# hub.net
KiCad netlist of a schematic drawn in Altium Designer
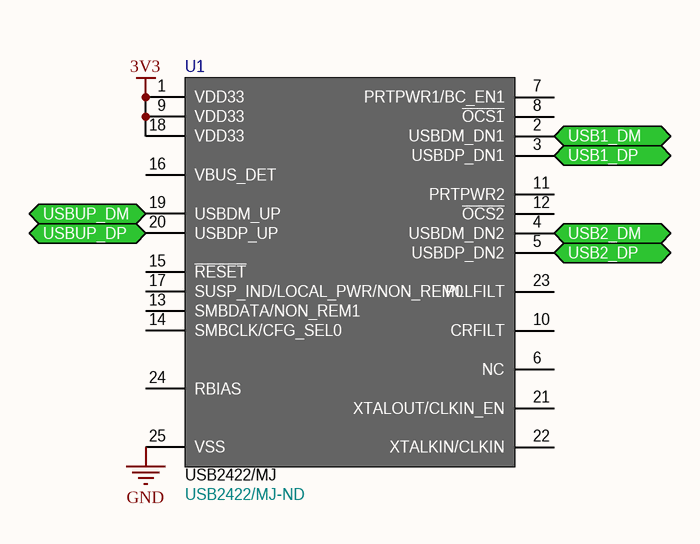
[diagram p0: hub.SchDoc]

(export (version "E")
  (design (tool "Eeschema 10.0.6"))
  (components
    (comp (ref "U1")
      (value "USB2422/MJ")
      (footprint "QFN50P400X400-24V2N")
      (description "IC HUB CTLR USB 2.0 24QFN")
      (fields
        (field (name "MANUFACTURER") "Microchip Technology")
        (field (name "BASE PART NUMBER") "USB2422")
        (field (name "SUPPLIER PART NUMBER 1") "USB2422/MJ-ND")
      )
      (libsource (lib "Microchip Interface") (part "USB2422/MJ"))
    )
  )
  (nets
    (net (code "1") (name "/USB1_DM") (class "Default")
      (node (ref "U1") (pin "2") (pinfunction "USBDM_DN1_2") (pintype "passive"))
    )
    (net (code "2") (name "/USB1_DP") (class "Default")
      (node (ref "U1") (pin "3") (pinfunction "USBDP_DN1_3") (pintype "passive"))
    )
    (net (code "3") (name "/USB2_DM") (class "Default")
      (node (ref "U1") (pin "4") (pinfunction "USBDM_DN2_4") (pintype "passive"))
    )
    (net (code "4") (name "/USB2_DP") (class "Default")
      (node (ref "U1") (pin "5") (pinfunction "USBDP_DN2_5") (pintype "passive"))
    )
    (net (code "5") (name "/USBUP_DM") (class "Default")
      (node (ref "U1") (pin "19") (pinfunction "USBDM_UP_19") (pintype "passive"))
    )
    (net (code "6") (name "/USBUP_DP") (class "Default")
      (node (ref "U1") (pin "20") (pinfunction "USBDP_UP_20") (pintype "passive"))
    )
    (net (code "7") (name "3V3") (class "Default")
      (node (ref "U1") (pin "1") (pinfunction "VDD33_1") (pintype "passive"))
      (node (ref "U1") (pin "18") (pinfunction "VDD33_18") (pintype "passive"))
      (node (ref "U1") (pin "9") (pinfunction "VDD33_9") (pintype "passive"))
    )
    (net (code "8") (name "GND") (class "Default")
      (node (ref "U1") (pin "25") (pinfunction "VSS_25") (pintype "passive"))
    )
    (net (code "9") (name "unconnected-(U1-CRFILT-Pad10)") (class "Default")
      (node (ref "U1") (pin "10") (pinfunction "CRFILT_10") (pintype "passive"))
    )
    (net (code "10") (name "unconnected-(U1-NC-Pad6)") (class "Default")
      (node (ref "U1") (pin "6") (pinfunction "NC_6") (pintype "passive"))
    )
    (net (code "11") (name "unconnected-(U1-PLLFILT-Pad23)") (class "Default")
      (node (ref "U1") (pin "23") (pinfunction "PLLFILT_23") (pintype "passive"))
    )
    (net (code "12") (name "unconnected-(U1-PRTPWR1{slash}BC_EN1-Pad7)") (class "Default")
      (node (ref "U1") (pin "7") (pinfunction "PRTPWR1/BC_EN1_7") (pintype "passive"))
    )
    (net (code "13") (name "unconnected-(U1-PRTPWR2-Pad11)") (class "Default")
      (node (ref "U1") (pin "11") (pinfunction "PRTPWR2_11") (pintype "passive"))
    )
    (net (code "14") (name "unconnected-(U1-RBIAS-Pad24)") (class "Default")
      (node (ref "U1") (pin "24") (pinfunction "RBIAS_24") (pintype "passive"))
    )
    (net (code "15") (name "unconnected-(U1-SMBCLK{slash}CFG_SEL0-Pad14)") (class "Default")
      (node (ref "U1") (pin "14") (pinfunction "SMBCLK/CFG_SEL0_14") (pintype "passive"))
    )
    (net (code "16") (name "unconnected-(U1-SMBDATA{slash}NON_REM1-Pad13)") (class "Default")
      (node (ref "U1") (pin "13") (pinfunction "SMBDATA/NON_REM1_13") (pintype "passive"))
    )
    (net (code "17") (name "unconnected-(U1-SUSP_IND{slash}LOCAL_PWR{slash}NON_REM0-Pad17)") (class "Default")
      (node (ref "U1") (pin "17") (pinfunction "SUSP_IND/LOCAL_PWR/NON_REM0_17") (pintype "passive"))
    )
    (net (code "18") (name "unconnected-(U1-VBUS_DET-Pad16)") (class "Default")
      (node (ref "U1") (pin "16") (pinfunction "VBUS_DET_16") (pintype "passive"))
    )
    (net (code "19") (name "unconnected-(U1-XTALKIN{slash}CLKIN-Pad22)") (class "Default")
      (node (ref "U1") (pin "22") (pinfunction "XTALKIN/CLKIN_22") (pintype "passive"))
    )
    (net (code "20") (name "unconnected-(U1-XTALOUT{slash}CLKIN_EN-Pad21)") (class "Default")
      (node (ref "U1") (pin "21") (pinfunction "XTALOUT/CLKIN_EN_21") (pintype "passive"))
    )
    (net (code "21") (name "unconnected-(U1-~{OCS1}-Pad8)") (class "Default")
      (node (ref "U1") (pin "8") (pinfunction "~{OCS1}_8") (pintype "passive"))
    )
    (net (code "22") (name "unconnected-(U1-~{OCS2}-Pad12)") (class "Default")
      (node (ref "U1") (pin "12") (pinfunction "~{OCS2}_12") (pintype "passive"))
    )
    (net (code "23") (name "unconnected-(U1-~{RESET}-Pad15)") (class "Default")
      (node (ref "U1") (pin "15") (pinfunction "~{RESET}_15") (pintype "passive"))
    )
  )
)
